# Motor_Driver.net
KiCad netlist of a schematic drawn in Altium Designer
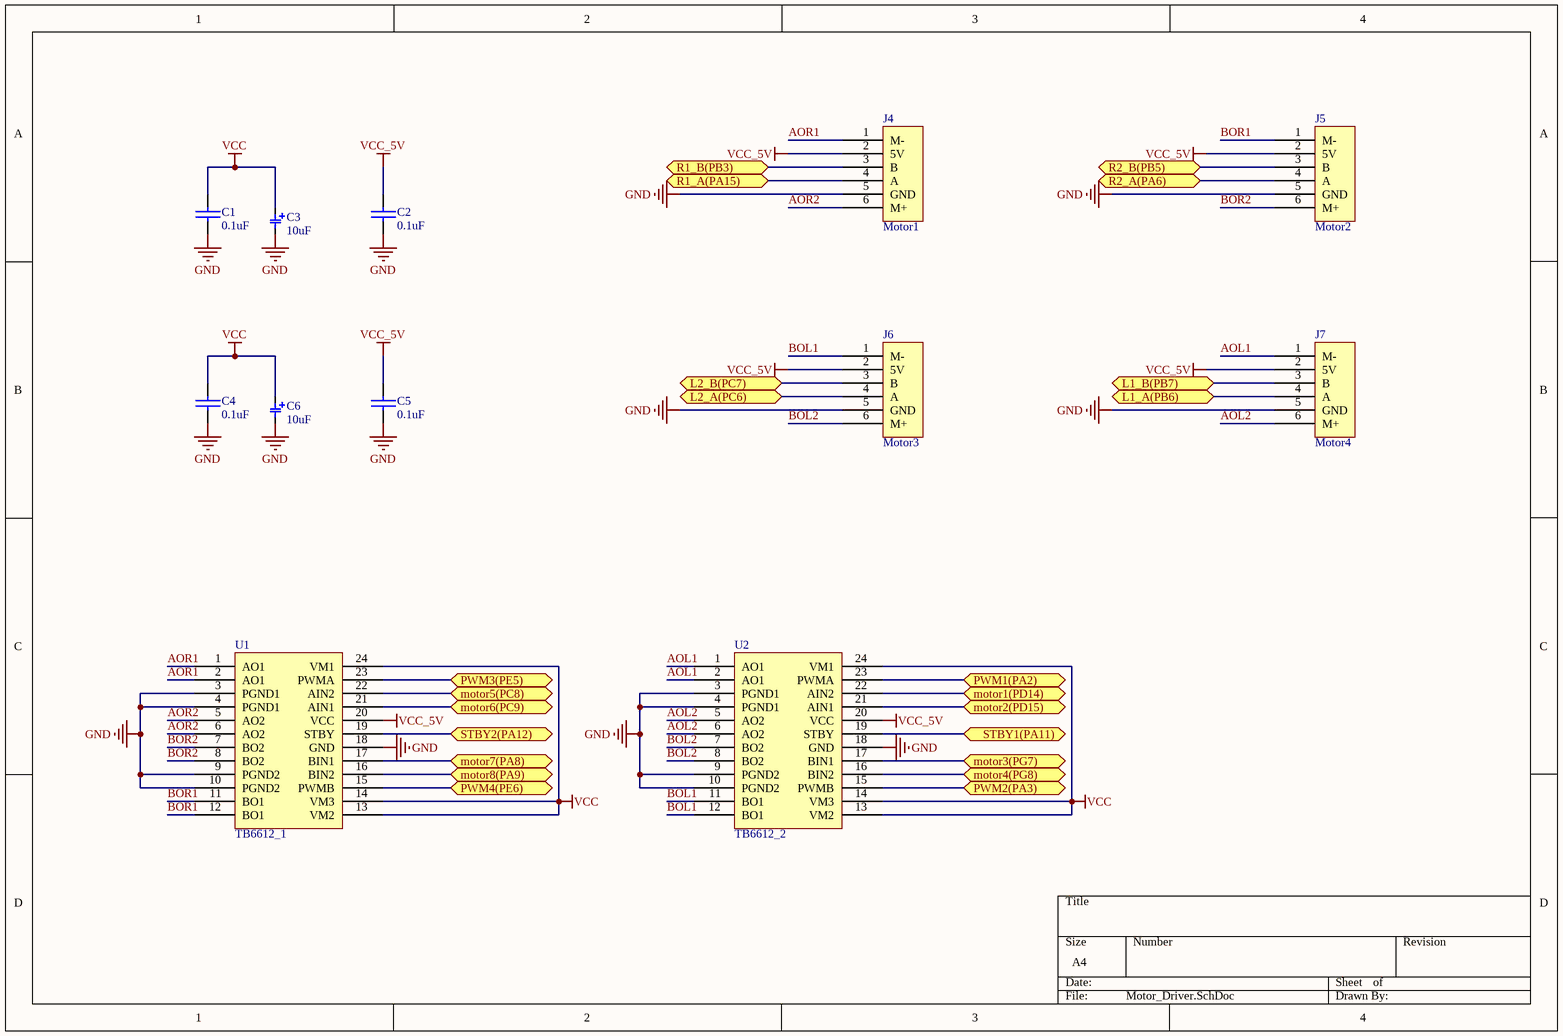
[diagram p0: Motor_Driver.SchDoc]

(export (version "E")
  (design (tool "Eeschema 10.0.6"))
  (components
    (comp (ref "C1")
      (value "0.1uF")
      (footprint "0603_C")
      (description "Capacitor")
      (libsource (lib "电容") (part "普通电容"))
    )
    (comp (ref "C2")
      (value "0.1uF")
      (footprint "0603_C")
      (description "Capacitor")
      (libsource (lib "电容") (part "普通电容"))
    )
    (comp (ref "C3") (value "10uF") (footprint "CASE-B_3528") (libsource (lib "电容") (part "ECAP")))
    (comp (ref "C4")
      (value "0.1uF")
      (footprint "0603_C")
      (description "Capacitor")
      (libsource (lib "电容") (part "普通电容"))
    )
    (comp (ref "C5")
      (value "0.1uF")
      (footprint "0603_C")
      (description "Capacitor")
      (libsource (lib "电容") (part "普通电容"))
    )
    (comp (ref "C6") (value "10uF") (footprint "CASE-B_3528") (libsource (lib "电容") (part "ECAP")))
    (comp (ref "J4")
      (value "Motor1")
      (footprint "XH2.54-WI-6P")
      (libsource (lib "ZH1.5") (part "Component_4"))
    )
    (comp (ref "J5")
      (value "Motor2")
      (footprint "XH2.54-WI-6P")
      (libsource (lib "ZH1.5") (part "Component_4"))
    )
    (comp (ref "J6")
      (value "Motor3")
      (footprint "XH2.54-WI-6P")
      (libsource (lib "ZH1.5") (part "Component_4"))
    )
    (comp (ref "J7")
      (value "Motor4")
      (footprint "XH2.54-WI-6P")
      (libsource (lib "ZH1.5") (part "Component_4"))
    )
    (comp (ref "U1")
      (value "TB6612_1")
      (footprint "SSOP-24_208mil")
      (libsource (lib "ZH1.5") (part "Component_3"))
    )
    (comp (ref "U2")
      (value "TB6612_2")
      (footprint "SSOP-24_208mil")
      (libsource (lib "ZH1.5") (part "Component_3"))
    )
  )
  (nets
    (net (code "1") (name "/AOL1") (class "Default")
      (node (ref "J7") (pin "1") (pinfunction "M-_1") (pintype "passive"))
      (node (ref "U2") (pin "1") (pinfunction "AO1_1") (pintype "passive"))
      (node (ref "U2") (pin "2") (pinfunction "AO1_2") (pintype "passive"))
    )
    (net (code "2") (name "/AOL2") (class "Default")
      (node (ref "J7") (pin "6") (pinfunction "M+_6") (pintype "passive"))
      (node (ref "U2") (pin "5") (pinfunction "AO2_5") (pintype "passive"))
      (node (ref "U2") (pin "6") (pinfunction "AO2_6") (pintype "passive"))
    )
    (net (code "3") (name "/AOR1") (class "Default")
      (node (ref "J4") (pin "1") (pinfunction "M-_1") (pintype "passive"))
      (node (ref "U1") (pin "1") (pinfunction "AO1_1") (pintype "passive"))
      (node (ref "U1") (pin "2") (pinfunction "AO1_2") (pintype "passive"))
    )
    (net (code "4") (name "/AOR2") (class "Default")
      (node (ref "J4") (pin "6") (pinfunction "M+_6") (pintype "passive"))
      (node (ref "U1") (pin "5") (pinfunction "AO2_5") (pintype "passive"))
      (node (ref "U1") (pin "6") (pinfunction "AO2_6") (pintype "passive"))
    )
    (net (code "5") (name "/BOL1") (class "Default")
      (node (ref "J6") (pin "1") (pinfunction "M-_1") (pintype "passive"))
      (node (ref "U2") (pin "11") (pinfunction "BO1_11") (pintype "passive"))
      (node (ref "U2") (pin "12") (pinfunction "BO1_12") (pintype "passive"))
    )
    (net (code "6") (name "/BOL2") (class "Default")
      (node (ref "J6") (pin "6") (pinfunction "M+_6") (pintype "passive"))
      (node (ref "U2") (pin "7") (pinfunction "BO2_7") (pintype "passive"))
      (node (ref "U2") (pin "8") (pinfunction "BO2_8") (pintype "passive"))
    )
    (net (code "7") (name "/BOR1") (class "Default")
      (node (ref "J5") (pin "1") (pinfunction "M-_1") (pintype "passive"))
      (node (ref "U1") (pin "11") (pinfunction "BO1_11") (pintype "passive"))
      (node (ref "U1") (pin "12") (pinfunction "BO1_12") (pintype "passive"))
    )
    (net (code "8") (name "/BOR2") (class "Default")
      (node (ref "J5") (pin "6") (pinfunction "M+_6") (pintype "passive"))
      (node (ref "U1") (pin "7") (pinfunction "BO2_7") (pintype "passive"))
      (node (ref "U1") (pin "8") (pinfunction "BO2_8") (pintype "passive"))
    )
    (net (code "9") (name "/L1_A(PB6)") (class "Default")
      (node (ref "J7") (pin "4") (pinfunction "A_4") (pintype "passive"))
    )
    (net (code "10") (name "/L1_B(PB7)") (class "Default")
      (node (ref "J7") (pin "3") (pinfunction "B_3") (pintype "passive"))
    )
    (net (code "11") (name "/L2_A(PC6)") (class "Default")
      (node (ref "J6") (pin "4") (pinfunction "A_4") (pintype "passive"))
    )
    (net (code "12") (name "/L2_B(PC7)") (class "Default")
      (node (ref "J6") (pin "3") (pinfunction "B_3") (pintype "passive"))
    )
    (net (code "13") (name "/PWM1(PA2)") (class "Default")
      (node (ref "U2") (pin "23") (pinfunction "PWMA_23") (pintype "passive"))
    )
    (net (code "14") (name "/PWM2(PA3)") (class "Default")
      (node (ref "U2") (pin "15") (pinfunction "PWMB_15") (pintype "passive"))
    )
    (net (code "15") (name "/PWM3(PE5)") (class "Default")
      (node (ref "U1") (pin "23") (pinfunction "PWMA_23") (pintype "passive"))
    )
    (net (code "16") (name "/PWM4(PE6)") (class "Default")
      (node (ref "U1") (pin "15") (pinfunction "PWMB_15") (pintype "passive"))
    )
    (net (code "17") (name "/R1_A(PA15)") (class "Default")
      (node (ref "J4") (pin "4") (pinfunction "A_4") (pintype "passive"))
    )
    (net (code "18") (name "/R1_B(PB3)") (class "Default")
      (node (ref "J4") (pin "3") (pinfunction "B_3") (pintype "passive"))
    )
    (net (code "19") (name "/R2_A(PA6)") (class "Default")
      (node (ref "J5") (pin "4") (pinfunction "A_4") (pintype "passive"))
    )
    (net (code "20") (name "/R2_B(PB5)") (class "Default")
      (node (ref "J5") (pin "3") (pinfunction "B_3") (pintype "passive"))
    )
    (net (code "21") (name "/STBY1(PA11)") (class "Default")
      (node (ref "U2") (pin "19") (pinfunction "STBY_19") (pintype "passive"))
    )
    (net (code "22") (name "/STBY2(PA12)") (class "Default")
      (node (ref "U1") (pin "19") (pinfunction "STBY_19") (pintype "passive"))
    )
    (net (code "23") (name "/motor1(PD14)") (class "Default")
      (node (ref "U2") (pin "22") (pinfunction "AIN2_22") (pintype "passive"))
    )
    (net (code "24") (name "/motor2(PD15)") (class "Default")
      (node (ref "U2") (pin "21") (pinfunction "AIN1_21") (pintype "passive"))
    )
    (net (code "25") (name "/motor3(PG7)") (class "Default")
      (node (ref "U2") (pin "17") (pinfunction "BIN1_17") (pintype "passive"))
    )
    (net (code "26") (name "/motor4(PG8)") (class "Default")
      (node (ref "U2") (pin "16") (pinfunction "BIN2_16") (pintype "passive"))
    )
    (net (code "27") (name "/motor5(PC8)") (class "Default")
      (node (ref "U1") (pin "22") (pinfunction "AIN2_22") (pintype "passive"))
    )
    (net (code "28") (name "/motor6(PC9)") (class "Default")
      (node (ref "U1") (pin "21") (pinfunction "AIN1_21") (pintype "passive"))
    )
    (net (code "29") (name "/motor7(PA8)") (class "Default")
      (node (ref "U1") (pin "17") (pinfunction "BIN1_17") (pintype "passive"))
    )
    (net (code "30") (name "/motor8(PA9)") (class "Default")
      (node (ref "U1") (pin "16") (pinfunction "BIN2_16") (pintype "passive"))
    )
    (net (code "31") (name "GND") (class "Default")
      (node (ref "C1") (pin "2") (pinfunction "2_2") (pintype "passive"))
      (node (ref "C2") (pin "2") (pinfunction "2_2") (pintype "passive"))
      (node (ref "C3") (pin "2") (pintype "passive"))
      (node (ref "C4") (pin "2") (pinfunction "2_2") (pintype "passive"))
      (node (ref "C5") (pin "2") (pinfunction "2_2") (pintype "passive"))
      (node (ref "C6") (pin "2") (pintype "passive"))
      (node (ref "J4") (pin "5") (pinfunction "GND_5") (pintype "passive"))
      (node (ref "J5") (pin "5") (pinfunction "GND_5") (pintype "passive"))
      (node (ref "J6") (pin "5") (pinfunction "GND_5") (pintype "passive"))
      (node (ref "J7") (pin "5") (pinfunction "GND_5") (pintype "passive"))
      (node (ref "U1") (pin "10") (pinfunction "PGND2_10") (pintype "passive"))
      (node (ref "U1") (pin "18") (pinfunction "GND_18") (pintype "passive"))
      (node (ref "U1") (pin "3") (pinfunction "PGND1_3") (pintype "passive"))
      (node (ref "U1") (pin "4") (pinfunction "PGND1_4") (pintype "passive"))
      (node (ref "U1") (pin "9") (pinfunction "PGND2_9") (pintype "passive"))
      (node (ref "U2") (pin "10") (pinfunction "PGND2_10") (pintype "passive"))
      (node (ref "U2") (pin "18") (pinfunction "GND_18") (pintype "passive"))
      (node (ref "U2") (pin "3") (pinfunction "PGND1_3") (pintype "passive"))
      (node (ref "U2") (pin "4") (pinfunction "PGND1_4") (pintype "passive"))
      (node (ref "U2") (pin "9") (pinfunction "PGND2_9") (pintype "passive"))
    )
    (net (code "32") (name "VCC") (class "Default")
      (node (ref "C1") (pin "1") (pinfunction "1_1") (pintype "passive"))
      (node (ref "C3") (pin "1") (pintype "passive"))
      (node (ref "C4") (pin "1") (pinfunction "1_1") (pintype "passive"))
      (node (ref "C6") (pin "1") (pintype "passive"))
      (node (ref "U1") (pin "13") (pinfunction "VM2_13") (pintype "passive"))
      (node (ref "U1") (pin "14") (pinfunction "VM3_14") (pintype "passive"))
      (node (ref "U1") (pin "24") (pinfunction "VM1_24") (pintype "passive"))
      (node (ref "U2") (pin "13") (pinfunction "VM2_13") (pintype "passive"))
      (node (ref "U2") (pin "14") (pinfunction "VM3_14") (pintype "passive"))
      (node (ref "U2") (pin "24") (pinfunction "VM1_24") (pintype "passive"))
    )
    (net (code "33") (name "VCC_5V") (class "Default")
      (node (ref "C2") (pin "1") (pinfunction "1_1") (pintype "passive"))
      (node (ref "C5") (pin "1") (pinfunction "1_1") (pintype "passive"))
      (node (ref "J4") (pin "2") (pinfunction "5V_2") (pintype "passive"))
      (node (ref "J5") (pin "2") (pinfunction "5V_2") (pintype "passive"))
      (node (ref "J6") (pin "2") (pinfunction "5V_2") (pintype "passive"))
      (node (ref "J7") (pin "2") (pinfunction "5V_2") (pintype "passive"))
      (node (ref "U1") (pin "20") (pinfunction "VCC_20") (pintype "passive"))
      (node (ref "U2") (pin "20") (pinfunction "VCC_20") (pintype "passive"))
    )
  )
)
